# regulation-level-shifter-mk-1_1.net
KiCad netlist of a schematic drawn in EAGLE
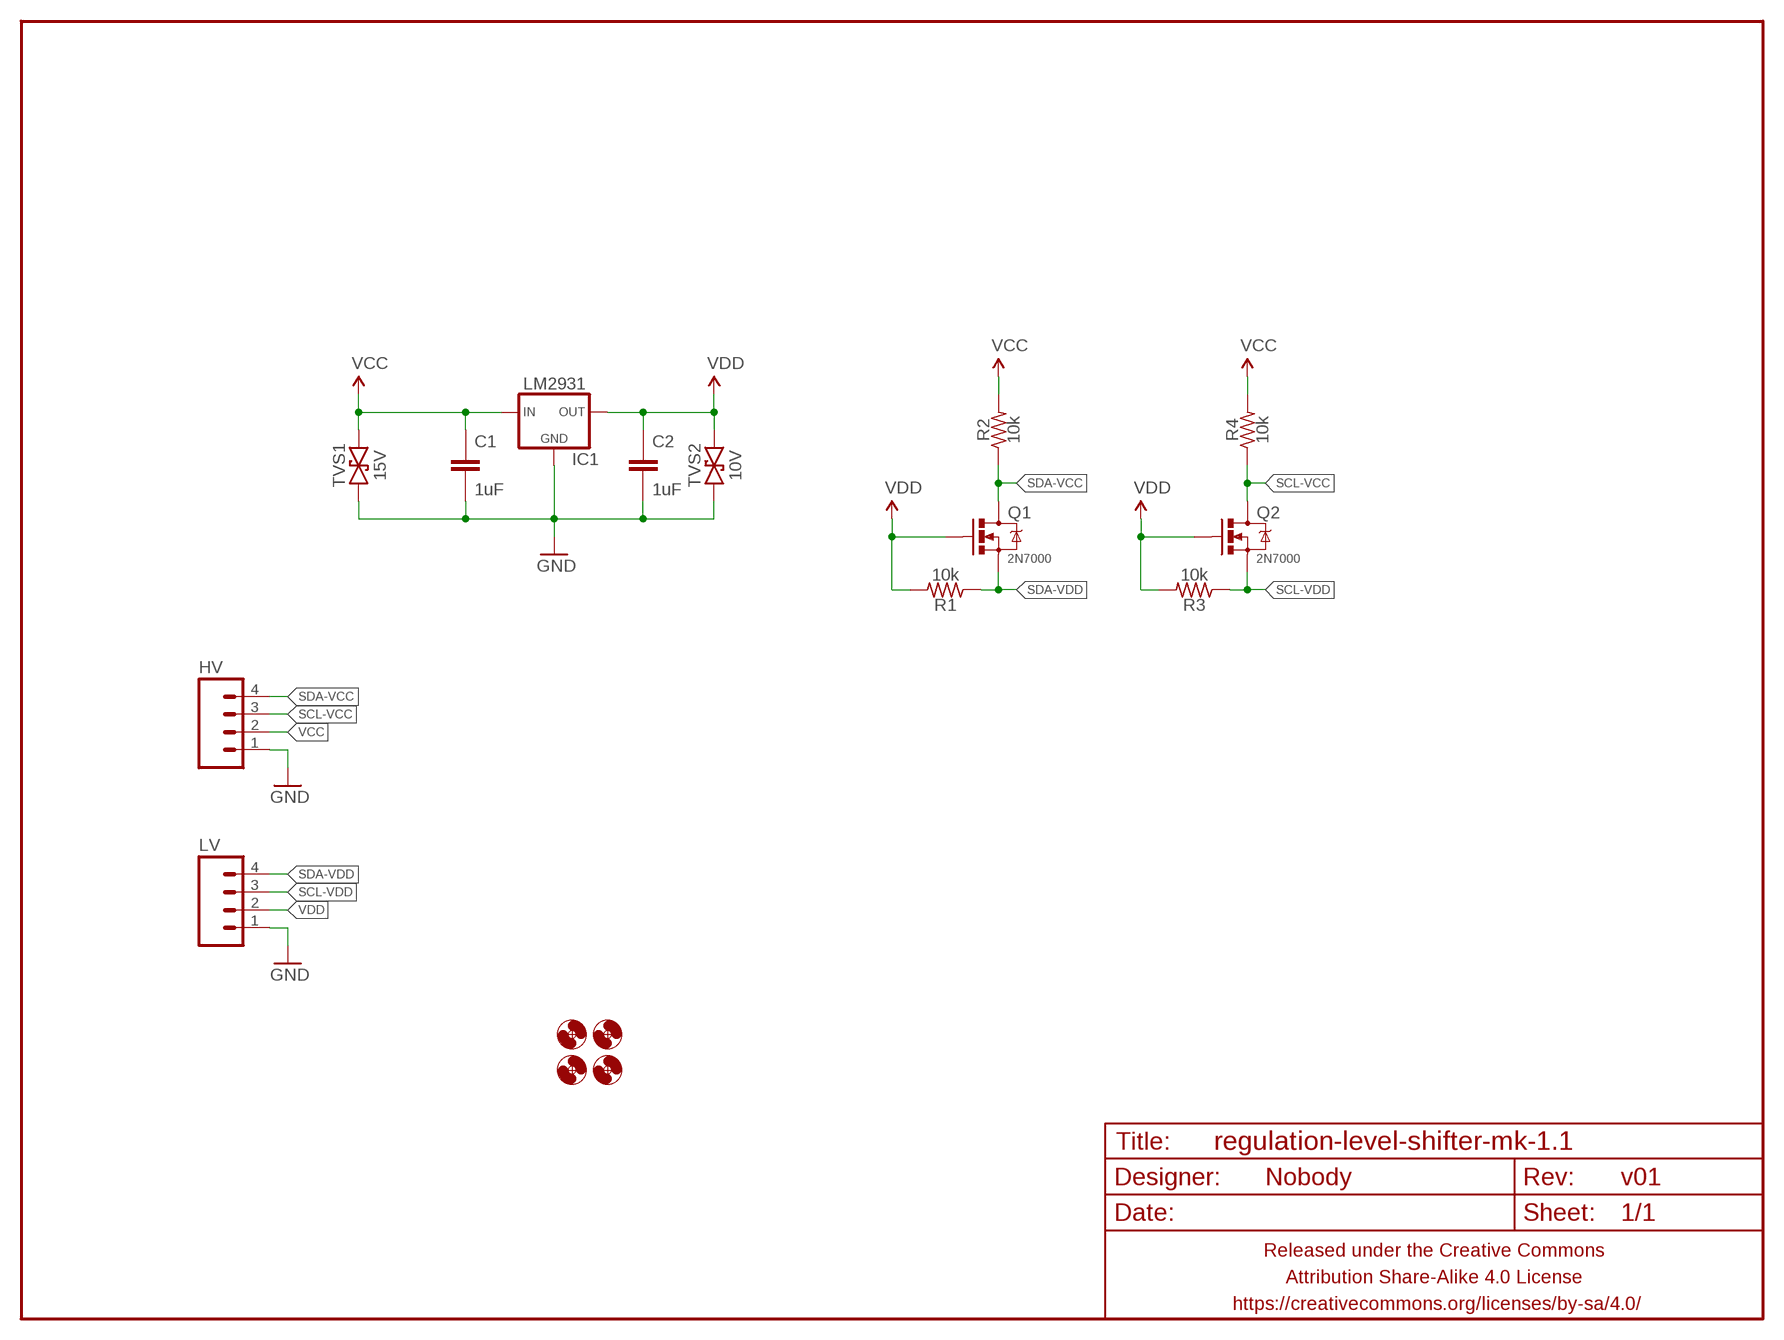
[diagram p0: schematic, sheet 1]

(export (version "E")
  (design (tool "Eeschema 10.0.6"))
  (components
    (comp (ref "C1")
      (value "1uF")
      (footprint "eagle-import:C025-024X044")
      (libsource (lib "eagle-import") (part "CAPACITOR-CERAMIC025-024X044"))
    )
    (comp (ref "C2")
      (value "1uF")
      (footprint "eagle-import:C025-024X044")
      (libsource (lib "eagle-import") (part "CAPACITOR-CERAMIC025-024X044"))
    )
    (comp (ref "FRAME1")
      (value "FRAME-LETTERNO_PACKAGE")
      (footprint "eagle-import:DUMMY")
      (fields (field (name "DESIGNER") "Nobody"))
      (libsource (lib "eagle-import") (part "FRAME-LETTERNO_PACKAGE"))
    )
    (comp (ref "H1")
      (value "HOLE#2")
      (footprint "eagle-import:HOLE-#2")
      (libsource (lib "eagle-import") (part "HOLE#2"))
    )
    (comp (ref "H2")
      (value "HOLE#2")
      (footprint "eagle-import:HOLE-#2")
      (libsource (lib "eagle-import") (part "HOLE#2"))
    )
    (comp (ref "H3")
      (value "HOLE#2")
      (footprint "eagle-import:HOLE-#2")
      (libsource (lib "eagle-import") (part "HOLE#2"))
    )
    (comp (ref "H4")
      (value "HOLE#2")
      (footprint "eagle-import:HOLE-#2")
      (libsource (lib "eagle-import") (part "HOLE#2"))
    )
    (comp (ref "HV")
      (value "M04PTH")
      (footprint "eagle-import:1X04-PTH-VERT")
      (libsource (lib "eagle-import") (part "M04PTH"))
    )
    (comp (ref "IC1")
      (value "LM2931")
      (footprint "eagle-import:TO-92-AMMO")
      (libsource (lib "eagle-import") (part "V_REG_78XXTO-92-INLINE"))
    )
    (comp (ref "LV")
      (value "M04PTH")
      (footprint "eagle-import:1X04-PTH-VERT")
      (libsource (lib "eagle-import") (part "M04PTH"))
    )
    (comp (ref "Q1")
      (value "2N7000")
      (footprint "eagle-import:TO-92-AMMO")
      (libsource (lib "eagle-import") (part "MOSFET-NCHANNEL2N7000-AMMO"))
    )
    (comp (ref "Q2")
      (value "2N7000")
      (footprint "eagle-import:TO-92-AMMO")
      (libsource (lib "eagle-import") (part "MOSFET-NCHANNEL2N7000-AMMO"))
    )
    (comp (ref "R1")
      (value "10k")
      (footprint "eagle-import:RESISTOR-AXIAL-PTH-5.08MM")
      (libsource (lib "eagle-import") (part "RESISTORPTH-AXIAL-5.08MM"))
    )
    (comp (ref "R2")
      (value "10k")
      (footprint "eagle-import:RESISTOR-AXIAL-PTH-5.08MM")
      (libsource (lib "eagle-import") (part "RESISTORPTH-AXIAL-5.08MM"))
    )
    (comp (ref "R3")
      (value "10k")
      (footprint "eagle-import:RESISTOR-AXIAL-PTH-5.08MM")
      (libsource (lib "eagle-import") (part "RESISTORPTH-AXIAL-5.08MM"))
    )
    (comp (ref "R4")
      (value "10k")
      (footprint "eagle-import:RESISTOR-AXIAL-PTH-5.08MM")
      (libsource (lib "eagle-import") (part "RESISTORPTH-AXIAL-5.08MM"))
    )
    (comp (ref "TVS1")
      (value "15V")
      (footprint "eagle-import:DO-41-TVS-BI-10.16MM")
      (libsource (lib "eagle-import") (part "TVSDO-41-10.16MM"))
    )
    (comp (ref "TVS2")
      (value "10V")
      (footprint "eagle-import:DO-41-TVS-BI-10.16MM")
      (libsource (lib "eagle-import") (part "TVSDO-41-10.16MM"))
    )
  )
  (nets
    (net (code "1") (name "GND") (class "Default")
      (node (ref "C1") (pin "2") (pinfunction "2_2") (pintype "passive"))
      (node (ref "C2") (pin "2") (pinfunction "2_2") (pintype "passive"))
      (node (ref "HV") (pin "1") (pinfunction "1_1") (pintype "passive"))
      (node (ref "IC1") (pin "2") (pinfunction "GND_2") (pintype "bidirectional"))
      (node (ref "LV") (pin "1") (pinfunction "1_1") (pintype "passive"))
      (node (ref "TVS1") (pin "P$1") (pinfunction "1_P$1") (pintype "passive"))
      (node (ref "TVS2") (pin "P$1") (pinfunction "1_P$1") (pintype "passive"))
    )
    (net (code "2") (name "SCL-VCC") (class "Default")
      (node (ref "HV") (pin "3") (pinfunction "3_3") (pintype "passive"))
      (node (ref "Q2") (pin "3") (pinfunction "D_3") (pintype "passive"))
      (node (ref "R4") (pin "P$1") (pinfunction "1_P$1") (pintype "passive"))
    )
    (net (code "3") (name "SCL-VDD") (class "Default")
      (node (ref "LV") (pin "3") (pinfunction "3_3") (pintype "passive"))
      (node (ref "Q2") (pin "1") (pinfunction "S_1") (pintype "passive"))
      (node (ref "R3") (pin "P$1") (pinfunction "1_P$1") (pintype "passive"))
    )
    (net (code "4") (name "SDA-VCC") (class "Default")
      (node (ref "HV") (pin "4") (pinfunction "4_4") (pintype "passive"))
      (node (ref "Q1") (pin "3") (pinfunction "D_3") (pintype "passive"))
      (node (ref "R2") (pin "P$1") (pinfunction "1_P$1") (pintype "passive"))
    )
    (net (code "5") (name "SDA-VDD") (class "Default")
      (node (ref "LV") (pin "4") (pinfunction "4_4") (pintype "passive"))
      (node (ref "Q1") (pin "1") (pinfunction "S_1") (pintype "passive"))
      (node (ref "R1") (pin "P$1") (pinfunction "1_P$1") (pintype "passive"))
    )
    (net (code "6") (name "VCC") (class "Default")
      (node (ref "C1") (pin "1") (pinfunction "1_1") (pintype "passive"))
      (node (ref "HV") (pin "2") (pinfunction "2_2") (pintype "passive"))
      (node (ref "IC1") (pin "1") (pinfunction "IN_1") (pintype "bidirectional"))
      (node (ref "R2") (pin "P$2") (pinfunction "2_P$2") (pintype "passive"))
      (node (ref "R4") (pin "P$2") (pinfunction "2_P$2") (pintype "passive"))
      (node (ref "TVS1") (pin "P$2") (pinfunction "2_P$2") (pintype "passive"))
    )
    (net (code "7") (name "VDD") (class "Default")
      (node (ref "C2") (pin "1") (pinfunction "1_1") (pintype "passive"))
      (node (ref "IC1") (pin "3") (pinfunction "OUT_3") (pintype "bidirectional"))
      (node (ref "LV") (pin "2") (pinfunction "2_2") (pintype "passive"))
      (node (ref "Q1") (pin "2") (pinfunction "G_2") (pintype "passive"))
      (node (ref "Q2") (pin "2") (pinfunction "G_2") (pintype "passive"))
      (node (ref "R1") (pin "P$2") (pinfunction "2_P$2") (pintype "passive"))
      (node (ref "R3") (pin "P$2") (pinfunction "2_P$2") (pintype "passive"))
      (node (ref "TVS2") (pin "P$2") (pinfunction "2_P$2") (pintype "passive"))
    )
  )
)
